# NTC_Measurement.net
KiCad netlist of a schematic drawn in Altium Designer
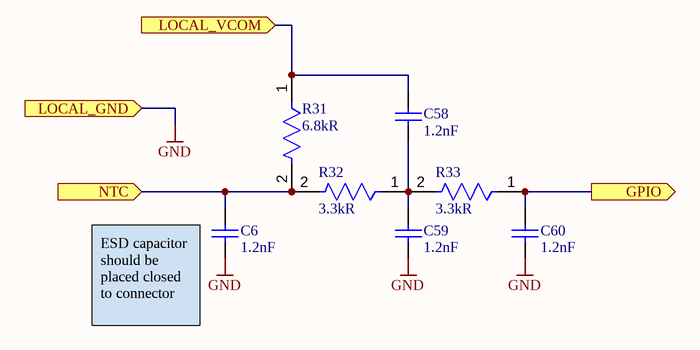
[diagram p0: NTC Measurement.SchDoc]

(export (version "E")
  (design (tool "Eeschema 10.0.6"))
  (components
    (comp (ref "C6")
      (value "1.2nF")
      (footprint "WCAP-CSGP_0402_L1W0.5H0.5")
      (description "WCAP-CSGP Multilayer Ceramic Chip Capacitor, General Purpose, size 0402, X7R, 1.2nF, 50VDC")
      (fields
        (field (name "MANUFACTURER PART NUMBER") "885012205092")
        (field (name "MANUFACTURER") "Wurth Elektronik")
      )
      (libsource (lib "Green Team Twente") (part "885012209047R"))
    )
    (comp (ref "C58")
      (value "1.2nF")
      (footprint "WCAP-CSGP_0402_L1W0.5H0.5")
      (description "WCAP-CSGP Multilayer Ceramic Chip Capacitor, General Purpose, size 0402, X7R, 1.2nF, 50VDC")
      (fields
        (field (name "MANUFACTURER PART NUMBER") "885012205092")
        (field (name "MANUFACTURER") "Wurth Elektronik")
      )
      (libsource (lib "Green Team Twente") (part "885012209047R"))
    )
    (comp (ref "C59")
      (value "1.2nF")
      (footprint "WCAP-CSGP_0402_L1W0.5H0.5")
      (description "WCAP-CSGP Multilayer Ceramic Chip Capacitor, General Purpose, size 0402, X7R, 1.2nF, 50VDC")
      (fields
        (field (name "MANUFACTURER PART NUMBER") "885012205092")
        (field (name "MANUFACTURER") "Wurth Elektronik")
      )
      (libsource (lib "Green Team Twente") (part "885012209047R"))
    )
    (comp (ref "C60")
      (value "1.2nF")
      (footprint "WCAP-CSGP_0402_L1W0.5H0.5")
      (description "WCAP-CSGP Multilayer Ceramic Chip Capacitor, General Purpose, size 0402, X7R, 1.2nF, 50VDC")
      (fields
        (field (name "MANUFACTURER PART NUMBER") "885012205092")
        (field (name "MANUFACTURER") "Wurth Elektronik")
      )
      (libsource (lib "Green Team Twente") (part "885012209047R"))
    )
    (comp (ref "R31")
      (value "6.8kR 0402 0.1%")
      (footprint "FP-RT0402-0_35-MFG")
      (description "RES SMD 6K8 OHM 0.1% 1/16W 0402")
      (fields (field (name "RESISTANCE") "6.8kR") (field (name "TOLERANCE") "0.1%"))
      (libsource (lib "Altium Content Vault") (part "1029c3af85768c4190bb7ad29bc67b5"))
    )
    (comp (ref "R32")
      (value "3.3R 0402 0.1%")
      (footprint "FP-RT0402-0_35-MFG")
      (description "RES SMD 3K3 OHM 0.1% 1/16W 0402")
      (fields (field (name "RESISTANCE") "3.3kR") (field (name "TOLERANCE") "0.1%"))
      (libsource (lib "Altium Content Vault") (part "1029c3af85768c4190bb7ad29bc67b5"))
    )
    (comp (ref "R33")
      (value "3.3R 0402 0.1%")
      (footprint "FP-RT0402-0_35-MFG")
      (description "RES SMD 3K3 OHM 0.1% 1/16W 0402")
      (fields (field (name "RESISTANCE") "3.3kR") (field (name "TOLERANCE") "0.1%"))
      (libsource (lib "Altium Content Vault") (part "1029c3af85768c4190bb7ad29bc67b5"))
    )
  )
  (nets
    (net (code "1") (name "/GPIO") (class "Default")
      (node (ref "C60") (pin "2") (pinfunction "2_2") (pintype "passive"))
      (node (ref "R33") (pin "1") (pinfunction "1_1") (pintype "passive"))
    )
    (net (code "2") (name "/LOCAL_VCOM") (class "Default")
      (node (ref "C58") (pin "2") (pinfunction "2_2") (pintype "passive"))
      (node (ref "R31") (pin "1") (pinfunction "1_1") (pintype "passive"))
    )
    (net (code "3") (name "/NTC") (class "Default")
      (node (ref "C6") (pin "2") (pinfunction "2_2") (pintype "passive"))
      (node (ref "R31") (pin "2") (pinfunction "2_2") (pintype "passive"))
      (node (ref "R32") (pin "2") (pinfunction "2_2") (pintype "passive"))
    )
    (net (code "4") (name "GND") (class "Default")
      (node (ref "C59") (pin "1") (pinfunction "1_1") (pintype "passive"))
      (node (ref "C6") (pin "1") (pinfunction "1_1") (pintype "passive"))
      (node (ref "C60") (pin "1") (pinfunction "1_1") (pintype "passive"))
    )
    (net (code "5") (name "Net-(C58-Pad1)") (class "Default")
      (node (ref "C58") (pin "1") (pinfunction "1_1") (pintype "passive"))
      (node (ref "C59") (pin "2") (pinfunction "2_2") (pintype "passive"))
      (node (ref "R32") (pin "1") (pinfunction "1_1") (pintype "passive"))
      (node (ref "R33") (pin "2") (pinfunction "2_2") (pintype "passive"))
    )
  )
)
